# axiom_beta_plugin_module_1xHDMI_v0_7_174.net
KiCad netlist of a schematic drawn in EAGLE
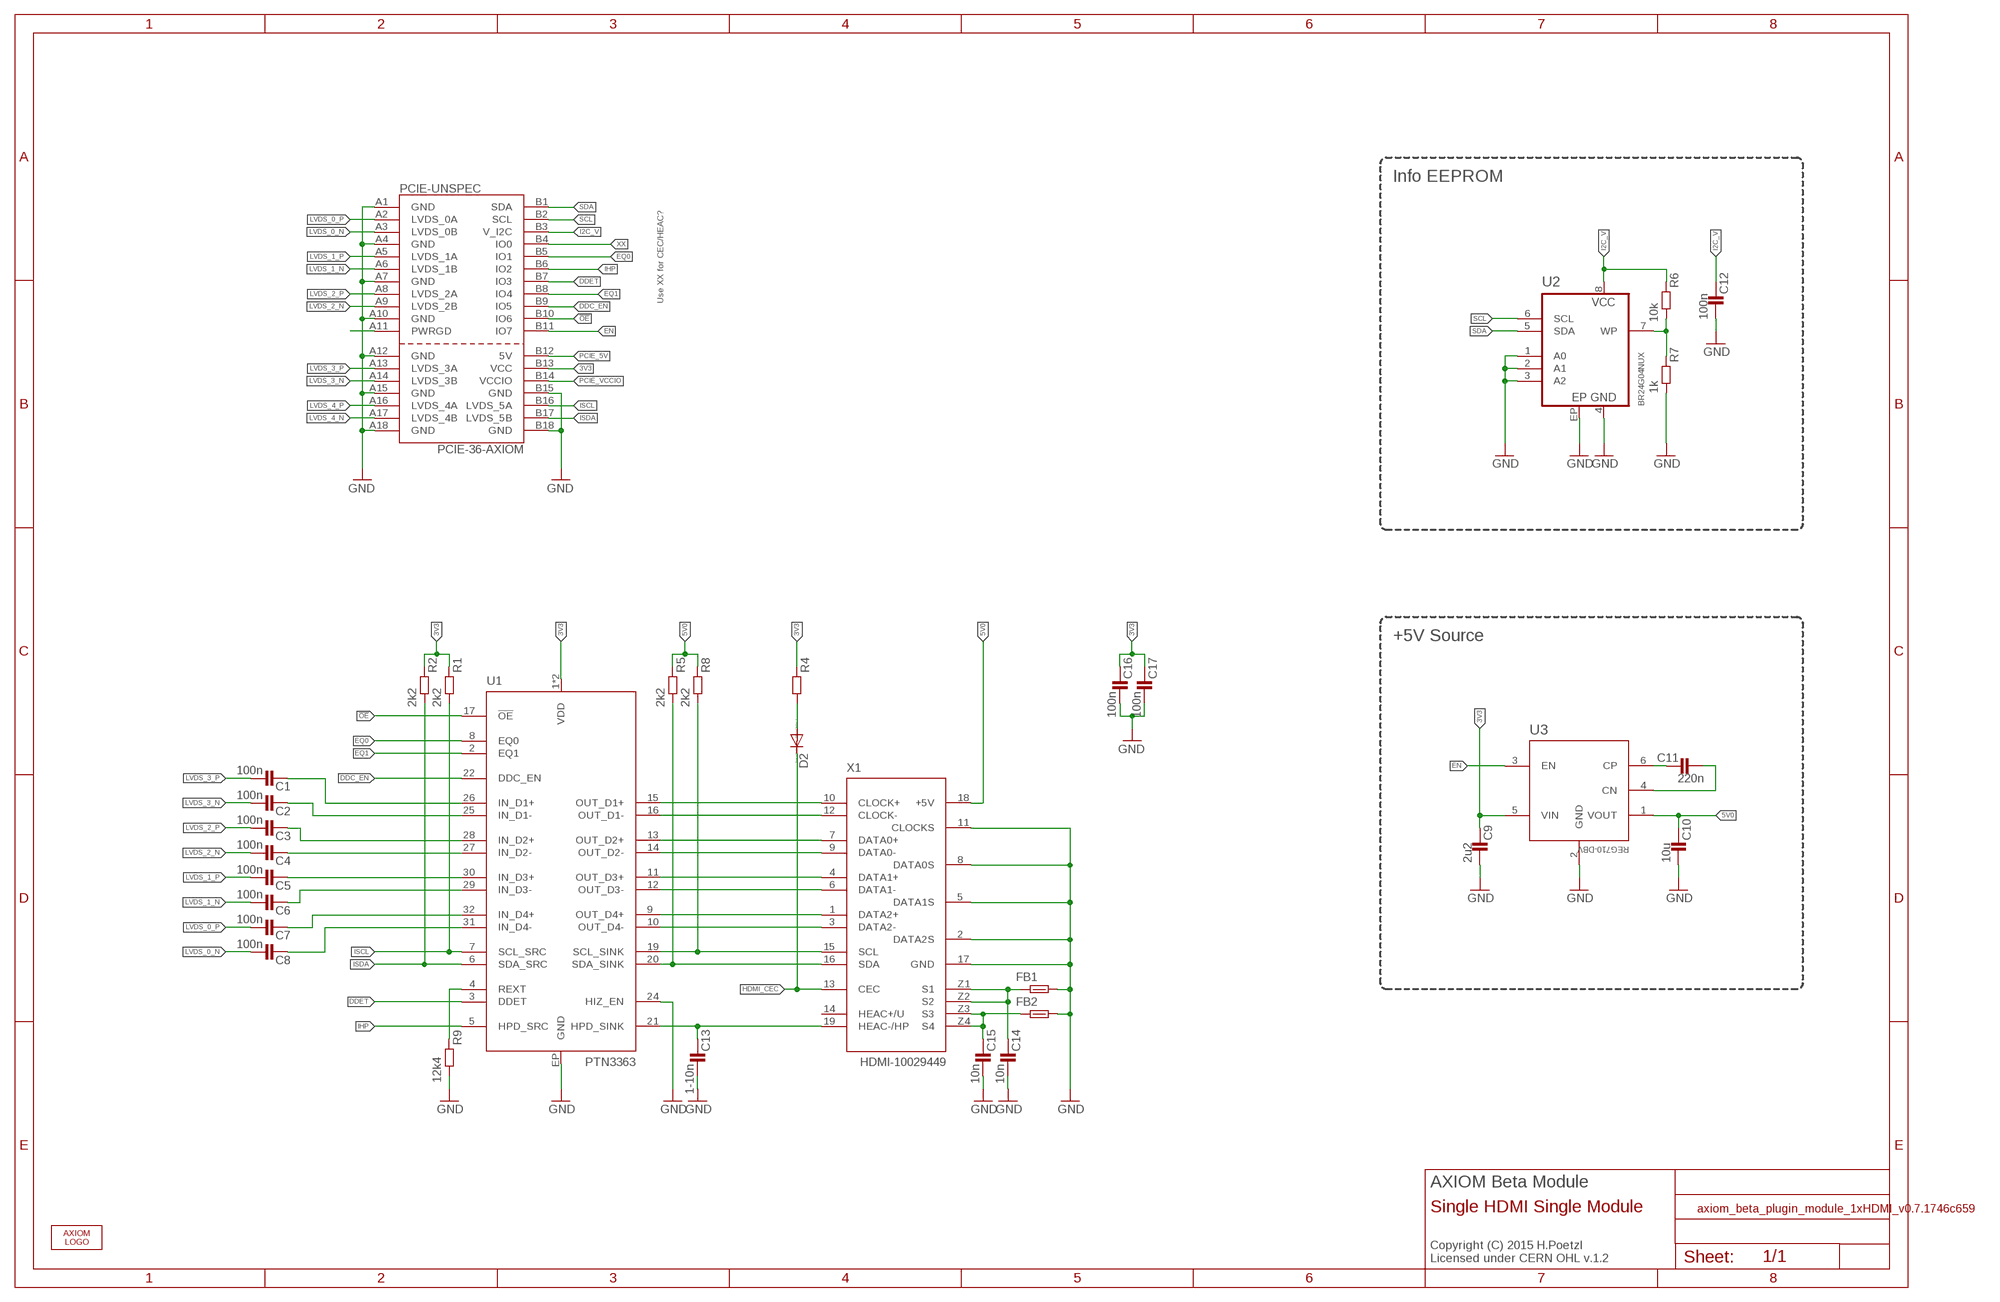
[diagram p0: schematic, sheet 1]

(export (version "E")
  (design (tool "Eeschema 10.0.6"))
  (components
    (comp (ref "C1")
      (value "100n")
      (footprint "eagle-import:0402-C")
      (libsource (lib "eagle-import") (part "C0402-C"))
    )
    (comp (ref "C2")
      (value "100n")
      (footprint "eagle-import:0402-C")
      (libsource (lib "eagle-import") (part "C0402-C"))
    )
    (comp (ref "C3")
      (value "100n")
      (footprint "eagle-import:0402-C")
      (libsource (lib "eagle-import") (part "C0402-C"))
    )
    (comp (ref "C4")
      (value "100n")
      (footprint "eagle-import:0402-C")
      (libsource (lib "eagle-import") (part "C0402-C"))
    )
    (comp (ref "C5")
      (value "100n")
      (footprint "eagle-import:0402-C")
      (libsource (lib "eagle-import") (part "C0402-C"))
    )
    (comp (ref "C6")
      (value "100n")
      (footprint "eagle-import:0402-C")
      (libsource (lib "eagle-import") (part "C0402-C"))
    )
    (comp (ref "C7")
      (value "100n")
      (footprint "eagle-import:0402-C")
      (libsource (lib "eagle-import") (part "C0402-C"))
    )
    (comp (ref "C8")
      (value "100n")
      (footprint "eagle-import:0402-C")
      (libsource (lib "eagle-import") (part "C0402-C"))
    )
    (comp (ref "C9")
      (value "2u2")
      (footprint "eagle-import:0603-B")
      (libsource (lib "eagle-import") (part "C0603-B"))
    )
    (comp (ref "C10")
      (value "10u")
      (footprint "eagle-import:0603-B")
      (libsource (lib "eagle-import") (part "C0603-B"))
    )
    (comp (ref "C11")
      (value "220n")
      (footprint "eagle-import:0603-B")
      (libsource (lib "eagle-import") (part "C0603-B"))
    )
    (comp (ref "C12")
      (value "100n")
      (footprint "eagle-import:0402-B")
      (libsource (lib "eagle-import") (part "C0402-B"))
    )
    (comp (ref "C13")
      (value "1-10n")
      (footprint "eagle-import:0402-B")
      (libsource (lib "eagle-import") (part "C0402-B"))
    )
    (comp (ref "C14")
      (value "10n")
      (footprint "eagle-import:0402-B")
      (libsource (lib "eagle-import") (part "C0402-B"))
    )
    (comp (ref "C15")
      (value "10n")
      (footprint "eagle-import:0402-B")
      (libsource (lib "eagle-import") (part "C0402-B"))
    )
    (comp (ref "C16")
      (value "100n")
      (footprint "eagle-import:0402-B")
      (libsource (lib "eagle-import") (part "C0402-B"))
    )
    (comp (ref "C17")
      (value "100n")
      (footprint "eagle-import:0402-B")
      (libsource (lib "eagle-import") (part "C0402-B"))
    )
    (comp (ref "D2")
      (value "DIODE-SOD523")
      (footprint "eagle-import:SOD523")
      (libsource (lib "eagle-import") (part "DIODE-SOD523"))
    )
    (comp (ref "FB1")
      (value "FB0603-B")
      (footprint "eagle-import:0603-B")
      (libsource (lib "eagle-import") (part "FB0603-B"))
    )
    (comp (ref "FB2")
      (value "FB0603-B")
      (footprint "eagle-import:0603-B")
      (libsource (lib "eagle-import") (part "FB0603-B"))
    )
    (comp (ref "PCIE-UNSPEC")
      (value "PCIE-36-AXIOM")
      (footprint "eagle-import:PCIE-36-AXIOM")
      (libsource (lib "eagle-import") (part "PCIE-36-AXIOM"))
    )
    (comp (ref "R1")
      (value "2k2")
      (footprint "eagle-import:0402-B")
      (libsource (lib "eagle-import") (part "R0402-B"))
    )
    (comp (ref "R2")
      (value "2k2")
      (footprint "eagle-import:0402-B")
      (libsource (lib "eagle-import") (part "R0402-B"))
    )
    (comp (ref "R4")
      (value "R0402-B")
      (footprint "eagle-import:0402-B")
      (libsource (lib "eagle-import") (part "R0402-B"))
    )
    (comp (ref "R5")
      (value "2k2")
      (footprint "eagle-import:0402-B")
      (libsource (lib "eagle-import") (part "R0402-B"))
    )
    (comp (ref "R6")
      (value "10k")
      (footprint "eagle-import:0402-B")
      (libsource (lib "eagle-import") (part "R0402-B"))
    )
    (comp (ref "R7")
      (value "1k")
      (footprint "eagle-import:0402-B")
      (libsource (lib "eagle-import") (part "R0402-B"))
    )
    (comp (ref "R8")
      (value "2k2")
      (footprint "eagle-import:0402-B")
      (libsource (lib "eagle-import") (part "R0402-B"))
    )
    (comp (ref "R9")
      (value "12k4")
      (footprint "eagle-import:0402-B")
      (libsource (lib "eagle-import") (part "R0402-B"))
    )
    (comp (ref "U$1")
      (value "AXIOM_LOGO459X70")
      (footprint "eagle-import:AXIOM_LOGO_459X70")
      (libsource (lib "eagle-import") (part "AXIOM_LOGO459X70"))
    )
    (comp (ref "U1")
      (value "PTN3363")
      (footprint "eagle-import:HVQFN32")
      (libsource (lib "eagle-import") (part "PTN3363"))
    )
    (comp (ref "U2")
      (value "BR24G04NUX")
      (footprint "eagle-import:DFN200X300X100-9N")
      (libsource (lib "eagle-import") (part "BR24G04NUX"))
    )
    (comp (ref "U3")
      (value "REG710-DBV")
      (footprint "eagle-import:DBV")
      (libsource (lib "eagle-import") (part "REG710-DBV"))
    )
    (comp (ref "X1")
      (value "HDMI-10029449")
      (footprint "eagle-import:10029449-X01XLF")
      (libsource (lib "eagle-import") (part "HDMI-10029449"))
    )
  )
  (nets
    (net (code "1") (name "/~{OE}") (class "Default")
      (node (ref "PCIE-UNSPEC") (pin "B10") (pinfunction "IO6_B10") (pintype "passive"))
      (node (ref "U1") (pin "17") (pinfunction "~{OE}_17") (pintype "bidirectional"))
    )
    (net (code "2") (name "3V3") (class "Default")
      (node (ref "C16") (pin "1") (pinfunction "1_1") (pintype "passive"))
      (node (ref "C17") (pin "1") (pinfunction "1_1") (pintype "passive"))
      (node (ref "C9") (pin "1") (pinfunction "1_1") (pintype "passive"))
      (node (ref "PCIE-UNSPEC") (pin "B13") (pinfunction "VCC_B13") (pintype "passive"))
      (node (ref "R1") (pin "1") (pinfunction "1_1") (pintype "passive"))
      (node (ref "R2") (pin "1") (pinfunction "1_1") (pintype "passive"))
      (node (ref "R4") (pin "1") (pinfunction "1_1") (pintype "passive"))
      (node (ref "U1") (pin "1") (pinfunction "VDD_1") (pintype "power_in"))
      (node (ref "U1") (pin "18") (pinfunction "VDD_18") (pintype "power_in"))
      (node (ref "U3") (pin "5") (pinfunction "VIN_5") (pintype "power_in"))
    )
    (net (code "3") (name "5V0") (class "Default")
      (node (ref "C10") (pin "1") (pinfunction "1_1") (pintype "passive"))
      (node (ref "R5") (pin "1") (pinfunction "1_1") (pintype "passive"))
      (node (ref "R8") (pin "1") (pinfunction "1_1") (pintype "passive"))
      (node (ref "U3") (pin "1") (pinfunction "VOUT_1") (pintype "output"))
      (node (ref "X1") (pin "18") (pinfunction "+5V_18") (pintype "power_in"))
    )
    (net (code "4") (name "DDC_EN") (class "Default")
      (node (ref "PCIE-UNSPEC") (pin "B9") (pinfunction "IO5_B9") (pintype "passive"))
      (node (ref "U1") (pin "22") (pinfunction "DDC_EN_22") (pintype "bidirectional"))
    )
    (net (code "5") (name "DDET") (class "Default")
      (node (ref "PCIE-UNSPEC") (pin "B7") (pinfunction "IO3_B7") (pintype "passive"))
      (node (ref "U1") (pin "3") (pinfunction "DDET_3") (pintype "bidirectional"))
    )
    (net (code "6") (name "EN") (class "Default")
      (node (ref "PCIE-UNSPEC") (pin "B11") (pinfunction "IO7_B11") (pintype "passive"))
      (node (ref "U3") (pin "3") (pinfunction "EN_3") (pintype "input"))
    )
    (net (code "7") (name "EQ0") (class "Default")
      (node (ref "PCIE-UNSPEC") (pin "B5") (pinfunction "IO1_B5") (pintype "passive"))
      (node (ref "U1") (pin "8") (pinfunction "EQ0_8") (pintype "bidirectional"))
    )
    (net (code "8") (name "EQ1") (class "Default")
      (node (ref "PCIE-UNSPEC") (pin "B8") (pinfunction "IO4_B8") (pintype "passive"))
      (node (ref "U1") (pin "2") (pinfunction "EQ1_2") (pintype "bidirectional"))
    )
    (net (code "9") (name "GND") (class "Default")
      (node (ref "C10") (pin "2") (pinfunction "2_2") (pintype "passive"))
      (node (ref "C12") (pin "2") (pinfunction "2_2") (pintype "passive"))
      (node (ref "C13") (pin "2") (pinfunction "2_2") (pintype "passive"))
      (node (ref "C14") (pin "2") (pinfunction "2_2") (pintype "passive"))
      (node (ref "C15") (pin "2") (pinfunction "2_2") (pintype "passive"))
      (node (ref "C16") (pin "2") (pinfunction "2_2") (pintype "passive"))
      (node (ref "C17") (pin "2") (pinfunction "2_2") (pintype "passive"))
      (node (ref "C9") (pin "2") (pinfunction "2_2") (pintype "passive"))
      (node (ref "FB1") (pin "2") (pinfunction "2_2") (pintype "passive"))
      (node (ref "FB2") (pin "2") (pinfunction "2_2") (pintype "passive"))
      (node (ref "PCIE-UNSPEC") (pin "A1") (pinfunction "GND_A1") (pintype "passive"))
      (node (ref "PCIE-UNSPEC") (pin "A10") (pinfunction "GND_A10") (pintype "passive"))
      (node (ref "PCIE-UNSPEC") (pin "A12") (pinfunction "GND_A12") (pintype "passive"))
      (node (ref "PCIE-UNSPEC") (pin "A15") (pinfunction "GND_A15") (pintype "passive"))
      (node (ref "PCIE-UNSPEC") (pin "A18") (pinfunction "GND_A18") (pintype "passive"))
      (node (ref "PCIE-UNSPEC") (pin "A4") (pinfunction "GND_A4") (pintype "passive"))
      (node (ref "PCIE-UNSPEC") (pin "A7") (pinfunction "GND_A7") (pintype "passive"))
      (node (ref "PCIE-UNSPEC") (pin "B15") (pinfunction "GND_B15") (pintype "passive"))
      (node (ref "PCIE-UNSPEC") (pin "B18") (pinfunction "GND_B18") (pintype "passive"))
      (node (ref "R7") (pin "2") (pinfunction "2_2") (pintype "passive"))
      (node (ref "R9") (pin "2") (pinfunction "2_2") (pintype "passive"))
      (node (ref "U1") (pin "24") (pinfunction "HIZ_EN_24") (pintype "bidirectional"))
      (node (ref "U1") (pin "EP") (pinfunction "GND_EP") (pintype "bidirectional"))
      (node (ref "U2") (pin "1") (pinfunction "A0_1") (pintype "input"))
      (node (ref "U2") (pin "2") (pinfunction "A1_2") (pintype "input"))
      (node (ref "U2") (pin "3") (pinfunction "A2_3") (pintype "input"))
      (node (ref "U2") (pin "4") (pinfunction "GND_4") (pintype "passive"))
      (node (ref "U2") (pin "EP") (pinfunction "EP_EP") (pintype "passive"))
      (node (ref "U3") (pin "2") (pinfunction "GND_2") (pintype "passive"))
      (node (ref "X1") (pin "11") (pinfunction "CLOCKS_11") (pintype "power_in"))
      (node (ref "X1") (pin "17") (pinfunction "GND_17") (pintype "bidirectional"))
      (node (ref "X1") (pin "2") (pinfunction "DATA2S_2") (pintype "power_in"))
      (node (ref "X1") (pin "5") (pinfunction "DATA1S_5") (pintype "power_in"))
      (node (ref "X1") (pin "8") (pinfunction "DATA0S_8") (pintype "power_in"))
    )
    (net (code "10") (name "HDMI_CEC") (class "Default")
      (node (ref "D2") (pin "C") (pinfunction "C_C") (pintype "passive"))
      (node (ref "X1") (pin "13") (pinfunction "CEC_13") (pintype "bidirectional"))
    )
    (net (code "11") (name "I2C_V") (class "Default")
      (node (ref "C12") (pin "1") (pinfunction "1_1") (pintype "passive"))
      (node (ref "PCIE-UNSPEC") (pin "B3") (pinfunction "V_I2C_B3") (pintype "passive"))
      (node (ref "R6") (pin "1") (pinfunction "1_1") (pintype "passive"))
      (node (ref "U2") (pin "8") (pinfunction "VCC_8") (pintype "power_in"))
    )
    (net (code "12") (name "IHP") (class "Default")
      (node (ref "PCIE-UNSPEC") (pin "B6") (pinfunction "IO2_B6") (pintype "passive"))
      (node (ref "U1") (pin "5") (pinfunction "HPD_SRC_5") (pintype "bidirectional"))
    )
    (net (code "13") (name "ISCL") (class "Default")
      (node (ref "PCIE-UNSPEC") (pin "B16") (pinfunction "LVDS_5A_B16") (pintype "passive"))
      (node (ref "R1") (pin "2") (pinfunction "2_2") (pintype "passive"))
      (node (ref "U1") (pin "7") (pinfunction "SCL_SRC_7") (pintype "bidirectional"))
    )
    (net (code "14") (name "ISDA") (class "Default")
      (node (ref "PCIE-UNSPEC") (pin "B17") (pinfunction "LVDS_5B_B17") (pintype "passive"))
      (node (ref "R2") (pin "2") (pinfunction "2_2") (pintype "passive"))
      (node (ref "U1") (pin "6") (pinfunction "SDA_SRC_6") (pintype "bidirectional"))
    )
    (net (code "15") (name "LVDS_0_N") (class "Default")
      (node (ref "C8") (pin "2") (pinfunction "2_2") (pintype "passive"))
      (node (ref "PCIE-UNSPEC") (pin "A3") (pinfunction "LVDS_0B_A3") (pintype "passive"))
    )
    (net (code "16") (name "LVDS_0_P") (class "Default")
      (node (ref "C7") (pin "2") (pinfunction "2_2") (pintype "passive"))
      (node (ref "PCIE-UNSPEC") (pin "A2") (pinfunction "LVDS_0A_A2") (pintype "passive"))
    )
    (net (code "17") (name "LVDS_1_N") (class "Default")
      (node (ref "C6") (pin "2") (pinfunction "2_2") (pintype "passive"))
      (node (ref "PCIE-UNSPEC") (pin "A6") (pinfunction "LVDS_1B_A6") (pintype "passive"))
    )
    (net (code "18") (name "LVDS_1_P") (class "Default")
      (node (ref "C5") (pin "2") (pinfunction "2_2") (pintype "passive"))
      (node (ref "PCIE-UNSPEC") (pin "A5") (pinfunction "LVDS_1A_A5") (pintype "passive"))
    )
    (net (code "19") (name "LVDS_2_N") (class "Default")
      (node (ref "C4") (pin "2") (pinfunction "2_2") (pintype "passive"))
      (node (ref "PCIE-UNSPEC") (pin "A9") (pinfunction "LVDS_2B_A9") (pintype "passive"))
    )
    (net (code "20") (name "LVDS_2_P") (class "Default")
      (node (ref "C3") (pin "2") (pinfunction "2_2") (pintype "passive"))
      (node (ref "PCIE-UNSPEC") (pin "A8") (pinfunction "LVDS_2A_A8") (pintype "passive"))
    )
    (net (code "21") (name "LVDS_3_N") (class "Default")
      (node (ref "C2") (pin "2") (pinfunction "2_2") (pintype "passive"))
      (node (ref "PCIE-UNSPEC") (pin "A14") (pinfunction "LVDS_3B_A14") (pintype "passive"))
    )
    (net (code "22") (name "LVDS_3_P") (class "Default")
      (node (ref "C1") (pin "2") (pinfunction "2_2") (pintype "passive"))
      (node (ref "PCIE-UNSPEC") (pin "A13") (pinfunction "LVDS_3A_A13") (pintype "passive"))
    )
    (net (code "23") (name "LVDS_4_N") (class "Default")
      (node (ref "PCIE-UNSPEC") (pin "A17") (pinfunction "LVDS_4B_A17") (pintype "passive"))
    )
    (net (code "24") (name "LVDS_4_P") (class "Default")
      (node (ref "PCIE-UNSPEC") (pin "A16") (pinfunction "LVDS_4A_A16") (pintype "passive"))
    )
    (net (code "25") (name "Net-(D2-PadA)") (class "Default")
      (node (ref "D2") (pin "A") (pinfunction "A_A") (pintype "passive"))
      (node (ref "R4") (pin "2") (pinfunction "2_2") (pintype "passive"))
    )
    (net (code "26") (name "Net-(U1-HPD_SINK)") (class "Default")
      (node (ref "C13") (pin "1") (pinfunction "1_1") (pintype "passive"))
      (node (ref "U1") (pin "21") (pinfunction "HPD_SINK_21") (pintype "bidirectional"))
      (node (ref "X1") (pin "19") (pinfunction "HEAC-/HP_19") (pintype "bidirectional"))
    )
    (net (code "27") (name "Net-(U1-IN_D1+)") (class "Default")
      (node (ref "C1") (pin "1") (pinfunction "1_1") (pintype "passive"))
      (node (ref "U1") (pin "26") (pinfunction "IN_D1+_26") (pintype "bidirectional"))
    )
    (net (code "28") (name "Net-(U1-IN_D1-)") (class "Default")
      (node (ref "C2") (pin "1") (pinfunction "1_1") (pintype "passive"))
      (node (ref "U1") (pin "25") (pinfunction "IN_D1-_25") (pintype "bidirectional"))
    )
    (net (code "29") (name "Net-(U1-IN_D2+)") (class "Default")
      (node (ref "C3") (pin "1") (pinfunction "1_1") (pintype "passive"))
      (node (ref "U1") (pin "28") (pinfunction "IN_D2+_28") (pintype "bidirectional"))
    )
    (net (code "30") (name "Net-(U1-IN_D2-)") (class "Default")
      (node (ref "C4") (pin "1") (pinfunction "1_1") (pintype "passive"))
      (node (ref "U1") (pin "27") (pinfunction "IN_D2-_27") (pintype "bidirectional"))
    )
    (net (code "31") (name "Net-(U1-IN_D3+)") (class "Default")
      (node (ref "C5") (pin "1") (pinfunction "1_1") (pintype "passive"))
      (node (ref "U1") (pin "30") (pinfunction "IN_D3+_30") (pintype "bidirectional"))
    )
    (net (code "32") (name "Net-(U1-IN_D3-)") (class "Default")
      (node (ref "C6") (pin "1") (pinfunction "1_1") (pintype "passive"))
      (node (ref "U1") (pin "29") (pinfunction "IN_D3-_29") (pintype "bidirectional"))
    )
    (net (code "33") (name "Net-(U1-IN_D4+)") (class "Default")
      (node (ref "C7") (pin "1") (pinfunction "1_1") (pintype "passive"))
      (node (ref "U1") (pin "32") (pinfunction "IN_D4+_32") (pintype "bidirectional"))
    )
    (net (code "34") (name "Net-(U1-IN_D4-)") (class "Default")
      (node (ref "C8") (pin "1") (pinfunction "1_1") (pintype "passive"))
      (node (ref "U1") (pin "31") (pinfunction "IN_D4-_31") (pintype "bidirectional"))
    )
    (net (code "35") (name "Net-(U1-OUT_D1+)") (class "Default")
      (node (ref "U1") (pin "15") (pinfunction "OUT_D1+_15") (pintype "bidirectional"))
      (node (ref "X1") (pin "10") (pinfunction "CLOCK+_10") (pintype "bidirectional"))
    )
    (net (code "36") (name "Net-(U1-OUT_D1-)") (class "Default")
      (node (ref "U1") (pin "16") (pinfunction "OUT_D1-_16") (pintype "bidirectional"))
      (node (ref "X1") (pin "12") (pinfunction "CLOCK-_12") (pintype "bidirectional"))
    )
    (net (code "37") (name "Net-(U1-OUT_D2+)") (class "Default")
      (node (ref "U1") (pin "13") (pinfunction "OUT_D2+_13") (pintype "bidirectional"))
      (node (ref "X1") (pin "7") (pinfunction "DATA0+_7") (pintype "bidirectional"))
    )
    (net (code "38") (name "Net-(U1-OUT_D2-)") (class "Default")
      (node (ref "U1") (pin "14") (pinfunction "OUT_D2-_14") (pintype "bidirectional"))
      (node (ref "X1") (pin "9") (pinfunction "DATA0-_9") (pintype "bidirectional"))
    )
    (net (code "39") (name "Net-(U1-OUT_D3+)") (class "Default")
      (node (ref "U1") (pin "11") (pinfunction "OUT_D3+_11") (pintype "bidirectional"))
      (node (ref "X1") (pin "4") (pinfunction "DATA1+_4") (pintype "bidirectional"))
    )
    (net (code "40") (name "Net-(U1-OUT_D3-)") (class "Default")
      (node (ref "U1") (pin "12") (pinfunction "OUT_D3-_12") (pintype "bidirectional"))
      (node (ref "X1") (pin "6") (pinfunction "DATA1-_6") (pintype "bidirectional"))
    )
    (net (code "41") (name "Net-(U1-OUT_D4+)") (class "Default")
      (node (ref "U1") (pin "9") (pinfunction "OUT_D4+_9") (pintype "bidirectional"))
      (node (ref "X1") (pin "1") (pinfunction "DATA2+_1") (pintype "bidirectional"))
    )
    (net (code "42") (name "Net-(U1-OUT_D4-)") (class "Default")
      (node (ref "U1") (pin "10") (pinfunction "OUT_D4-_10") (pintype "bidirectional"))
      (node (ref "X1") (pin "3") (pinfunction "DATA2-_3") (pintype "bidirectional"))
    )
    (net (code "43") (name "Net-(U1-REXT)") (class "Default")
      (node (ref "R9") (pin "1") (pinfunction "1_1") (pintype "passive"))
      (node (ref "U1") (pin "4") (pinfunction "REXT_4") (pintype "bidirectional"))
    )
    (net (code "44") (name "Net-(U1-SCL_SINK)") (class "Default")
      (node (ref "R8") (pin "2") (pinfunction "2_2") (pintype "passive"))
      (node (ref "U1") (pin "19") (pinfunction "SCL_SINK_19") (pintype "bidirectional"))
      (node (ref "X1") (pin "15") (pinfunction "SCL_15") (pintype "bidirectional"))
    )
    (net (code "45") (name "Net-(U1-SDA_SINK)") (class "Default")
      (node (ref "R5") (pin "2") (pinfunction "2_2") (pintype "passive"))
      (node (ref "U1") (pin "20") (pinfunction "SDA_SINK_20") (pintype "bidirectional"))
      (node (ref "X1") (pin "16") (pinfunction "SDA_16") (pintype "bidirectional"))
    )
    (net (code "46") (name "Net-(U2-WP)") (class "Default")
      (node (ref "R6") (pin "2") (pinfunction "2_2") (pintype "passive"))
      (node (ref "R7") (pin "1") (pinfunction "1_1") (pintype "passive"))
      (node (ref "U2") (pin "7") (pinfunction "WP_7") (pintype "input"))
    )
    (net (code "47") (name "Net-(U3-CN)") (class "Default")
      (node (ref "C11") (pin "2") (pinfunction "2_2") (pintype "passive"))
      (node (ref "U3") (pin "4") (pinfunction "CN_4") (pintype "power_in"))
    )
    (net (code "48") (name "Net-(U3-CP)") (class "Default")
      (node (ref "C11") (pin "1") (pinfunction "1_1") (pintype "passive"))
      (node (ref "U3") (pin "6") (pinfunction "CP_6") (pintype "output"))
    )
    (net (code "49") (name "Net-(X1-S1)") (class "Default")
      (node (ref "C14") (pin "1") (pinfunction "1_1") (pintype "passive"))
      (node (ref "FB1") (pin "1") (pinfunction "1_1") (pintype "passive"))
      (node (ref "X1") (pin "Z1") (pinfunction "S1_Z1") (pintype "power_in"))
      (node (ref "X1") (pin "Z2") (pinfunction "S2_Z2") (pintype "power_in"))
    )
    (net (code "50") (name "Net-(X1-S3)") (class "Default")
      (node (ref "C15") (pin "1") (pinfunction "1_1") (pintype "passive"))
      (node (ref "FB2") (pin "1") (pinfunction "1_1") (pintype "passive"))
      (node (ref "X1") (pin "Z3") (pinfunction "S3_Z3") (pintype "power_in"))
      (node (ref "X1") (pin "Z4") (pinfunction "S4_Z4") (pintype "power_in"))
    )
    (net (code "51") (name "PCIE_5V") (class "Default")
      (node (ref "PCIE-UNSPEC") (pin "B12") (pinfunction "5V_B12") (pintype "passive"))
    )
    (net (code "52") (name "PCIE_VCCIO") (class "Default")
      (node (ref "PCIE-UNSPEC") (pin "B14") (pinfunction "VCCIO_B14") (pintype "passive"))
    )
    (net (code "53") (name "SCL") (class "Default")
      (node (ref "PCIE-UNSPEC") (pin "B2") (pinfunction "SCL_B2") (pintype "passive"))
      (node (ref "U2") (pin "6") (pinfunction "SCL_6") (pintype "input"))
    )
    (net (code "54") (name "SDA") (class "Default")
      (node (ref "PCIE-UNSPEC") (pin "B1") (pinfunction "SDA_B1") (pintype "passive"))
      (node (ref "U2") (pin "5") (pinfunction "SDA_5") (pintype "bidirectional"))
    )
    (net (code "55") (name "XX") (class "Default")
      (node (ref "PCIE-UNSPEC") (pin "B4") (pinfunction "IO0_B4") (pintype "passive"))
    )
    (net (code "56") (name "unconnected-(PCIE-UNSPEC-PWRGD-PadA11)") (class "Default")
      (node (ref "PCIE-UNSPEC") (pin "A11") (pinfunction "PWRGD_A11") (pintype "passive"))
    )
    (net (code "57") (name "unconnected-(X1-HEAC+{slash}U-Pad14)") (class "Default")
      (node (ref "X1") (pin "14") (pinfunction "HEAC+/U_14") (pintype "bidirectional"))
    )
  )
)
